# fitnessBuddy-TOP.net
KiCad netlist of a schematic drawn in EAGLE
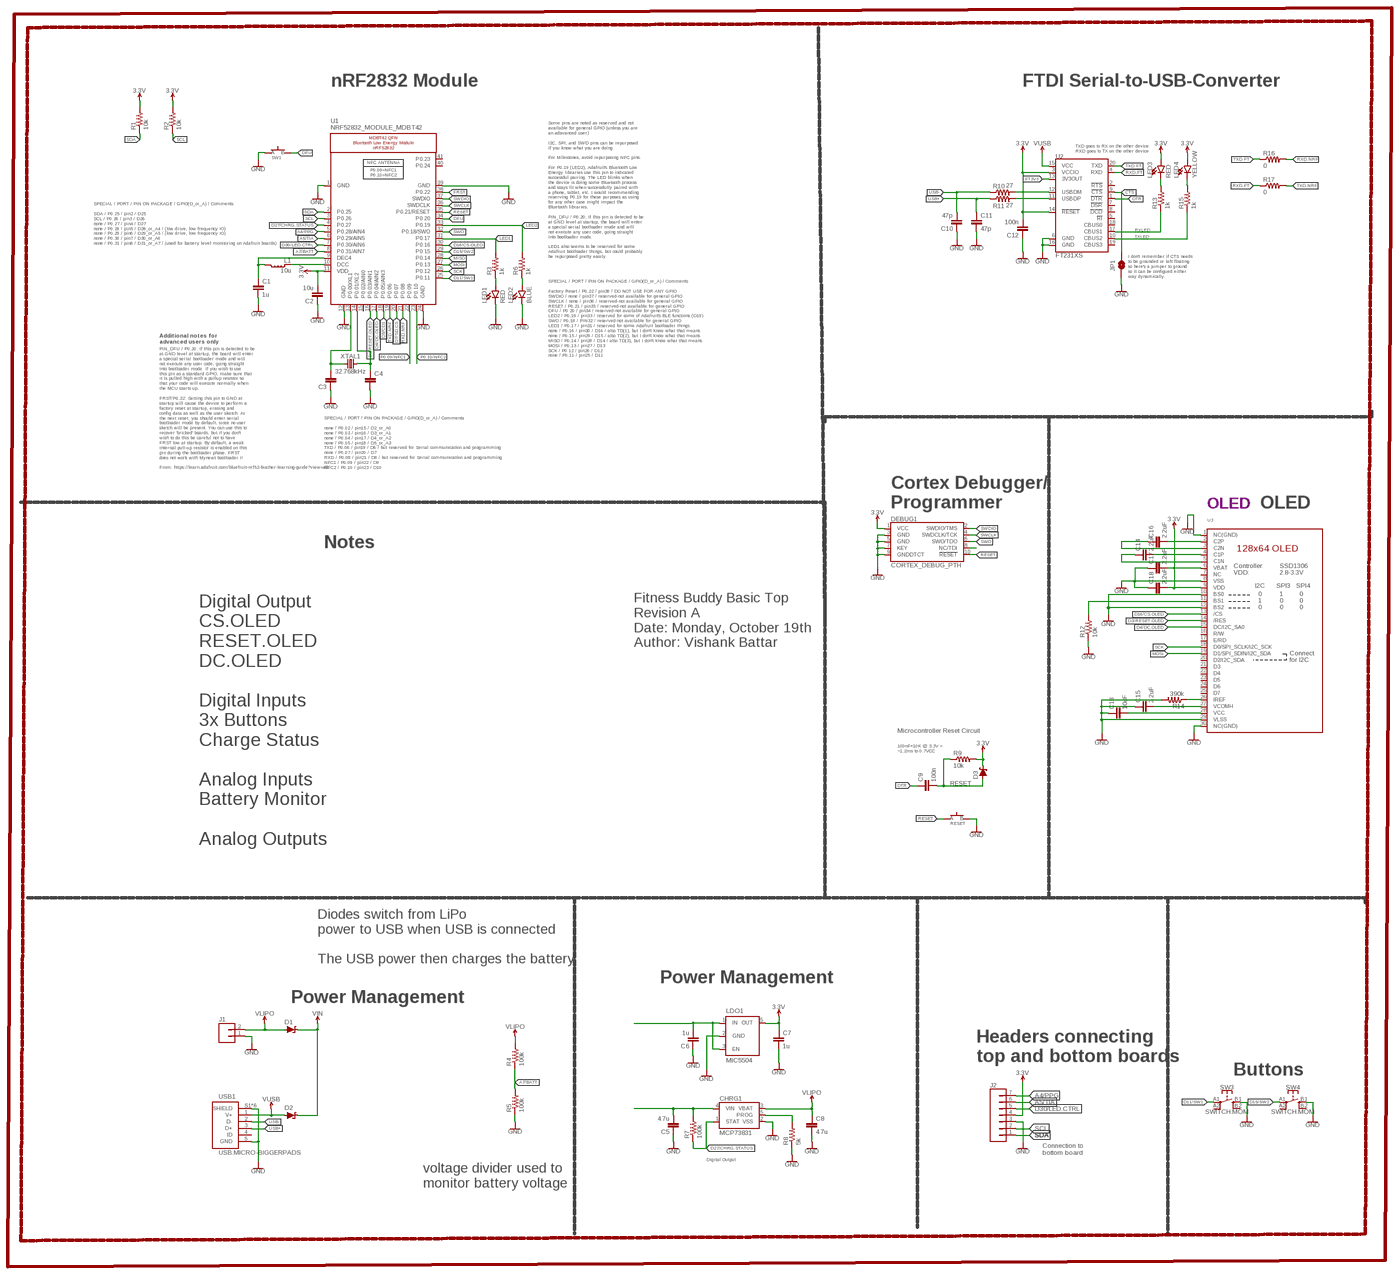
[diagram p0: schematic, sheet 1, overview]
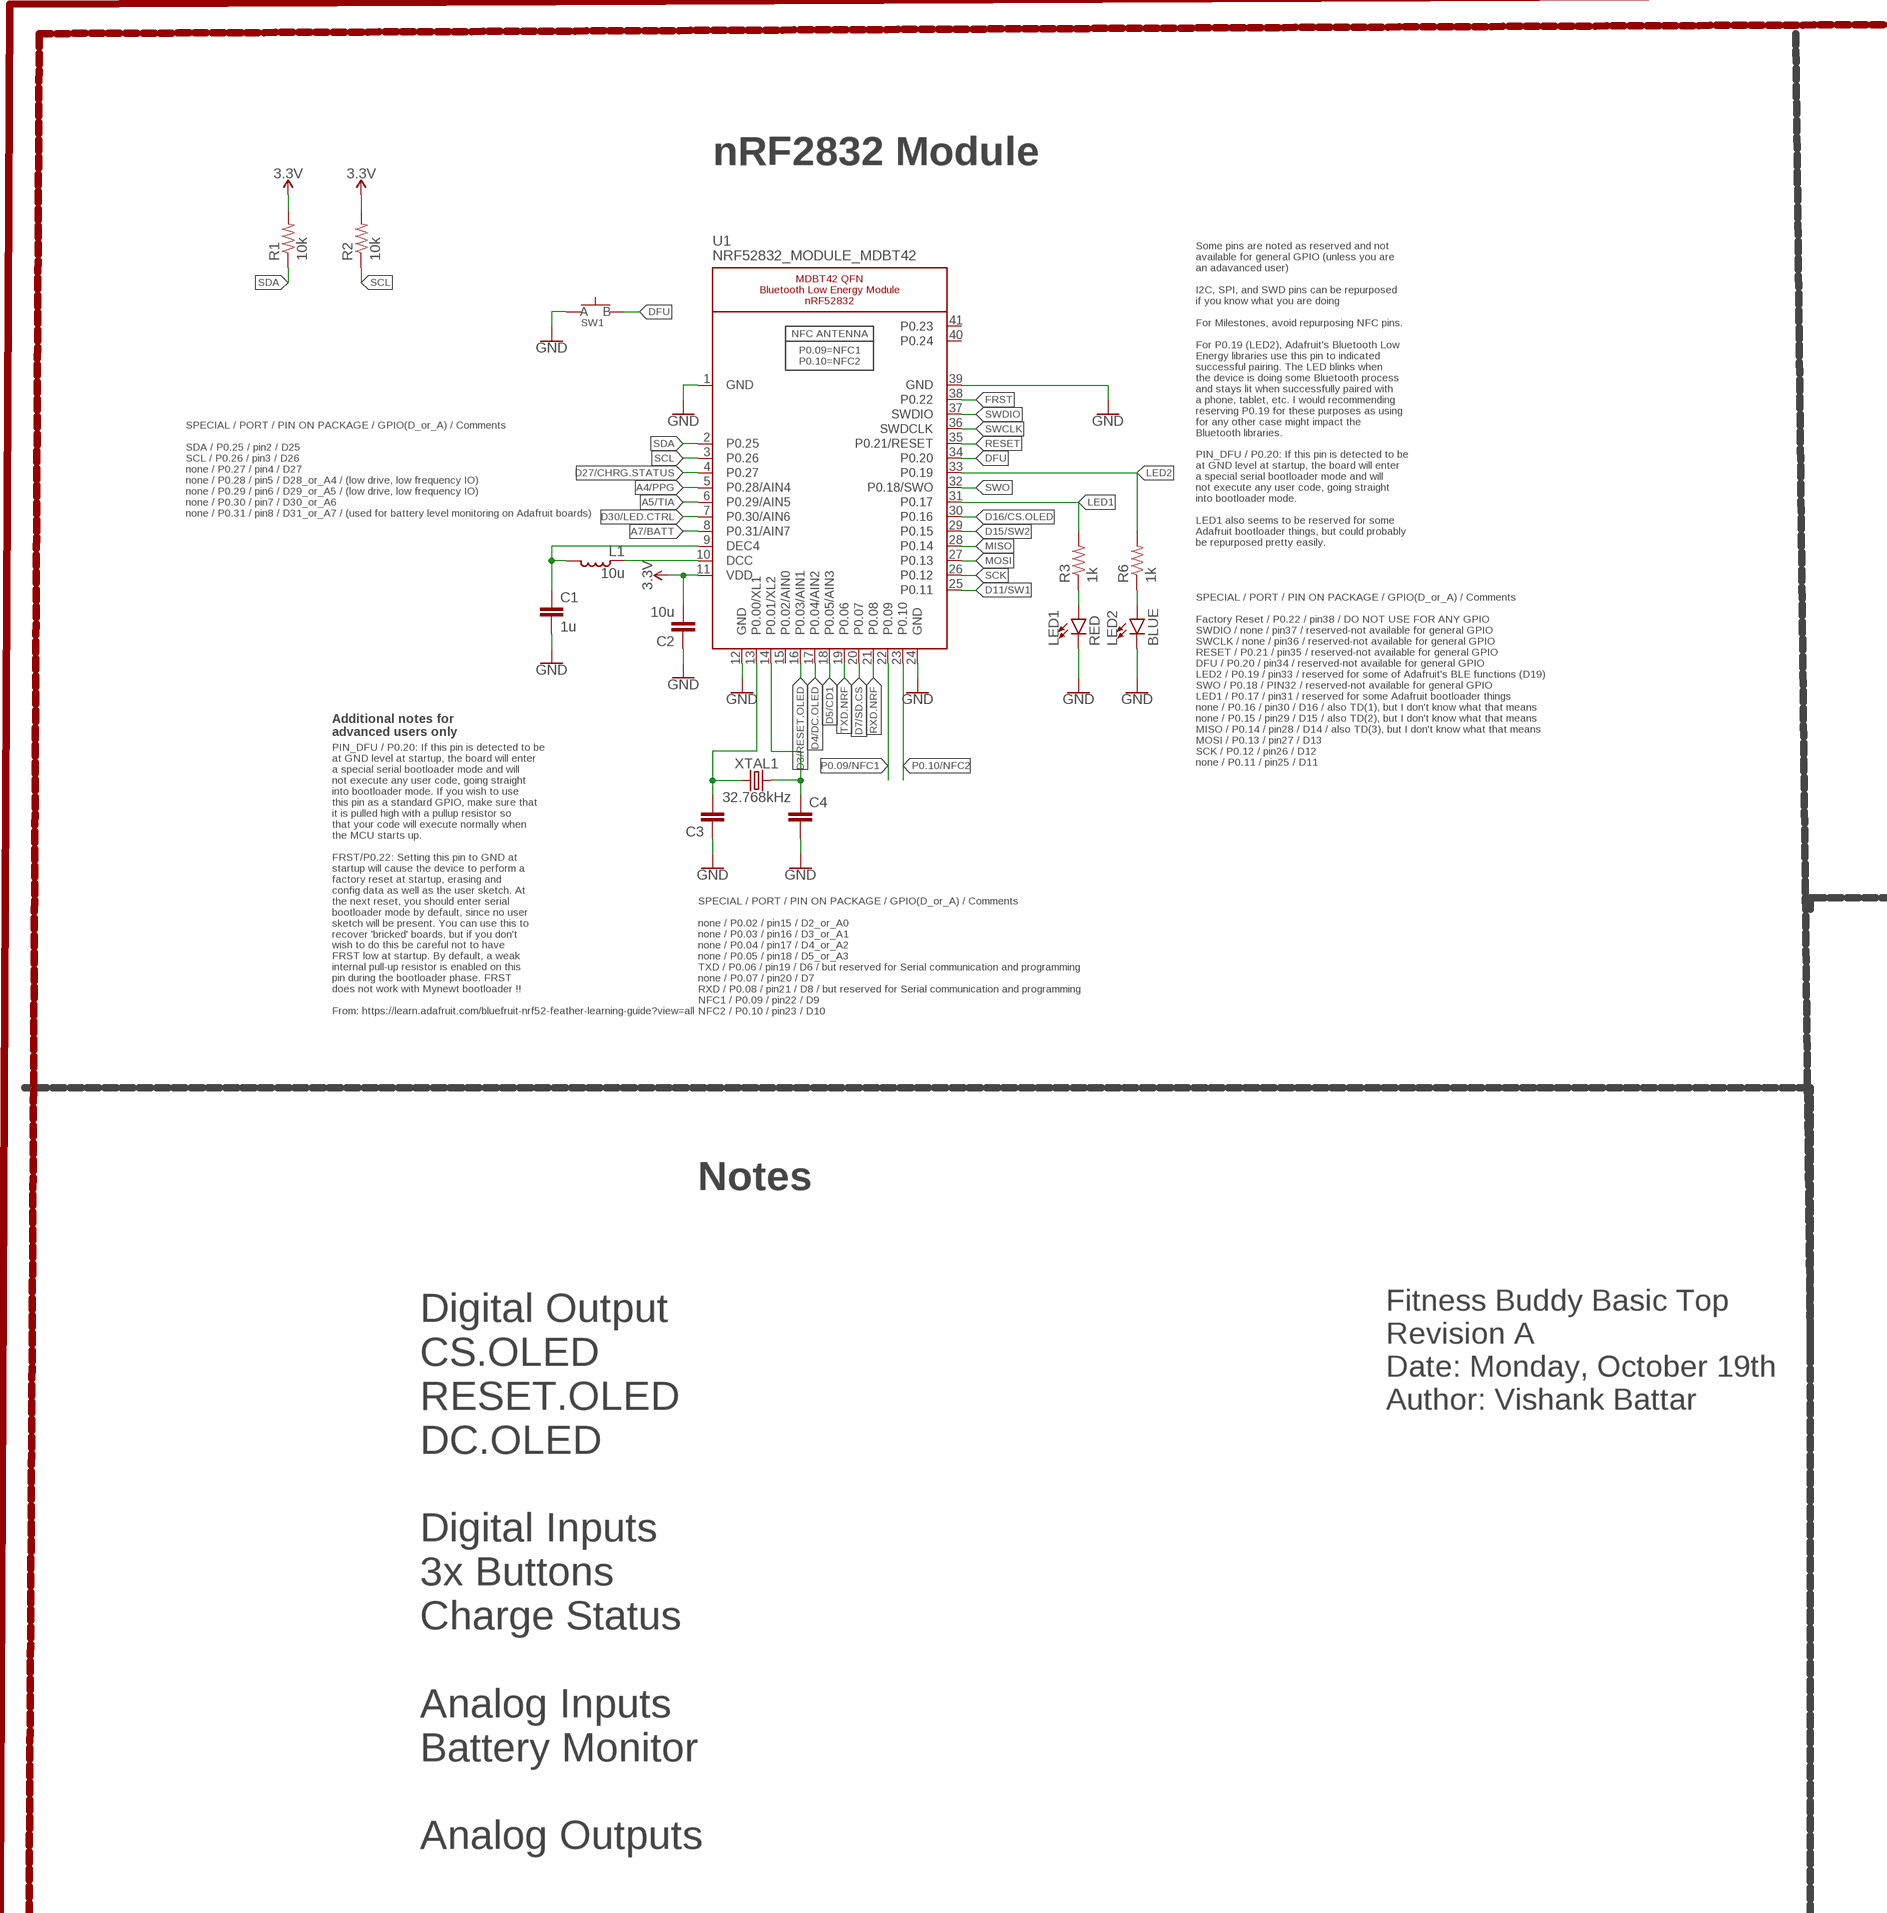
[diagram p1: schematic, sheet 1, part 1 of 4]
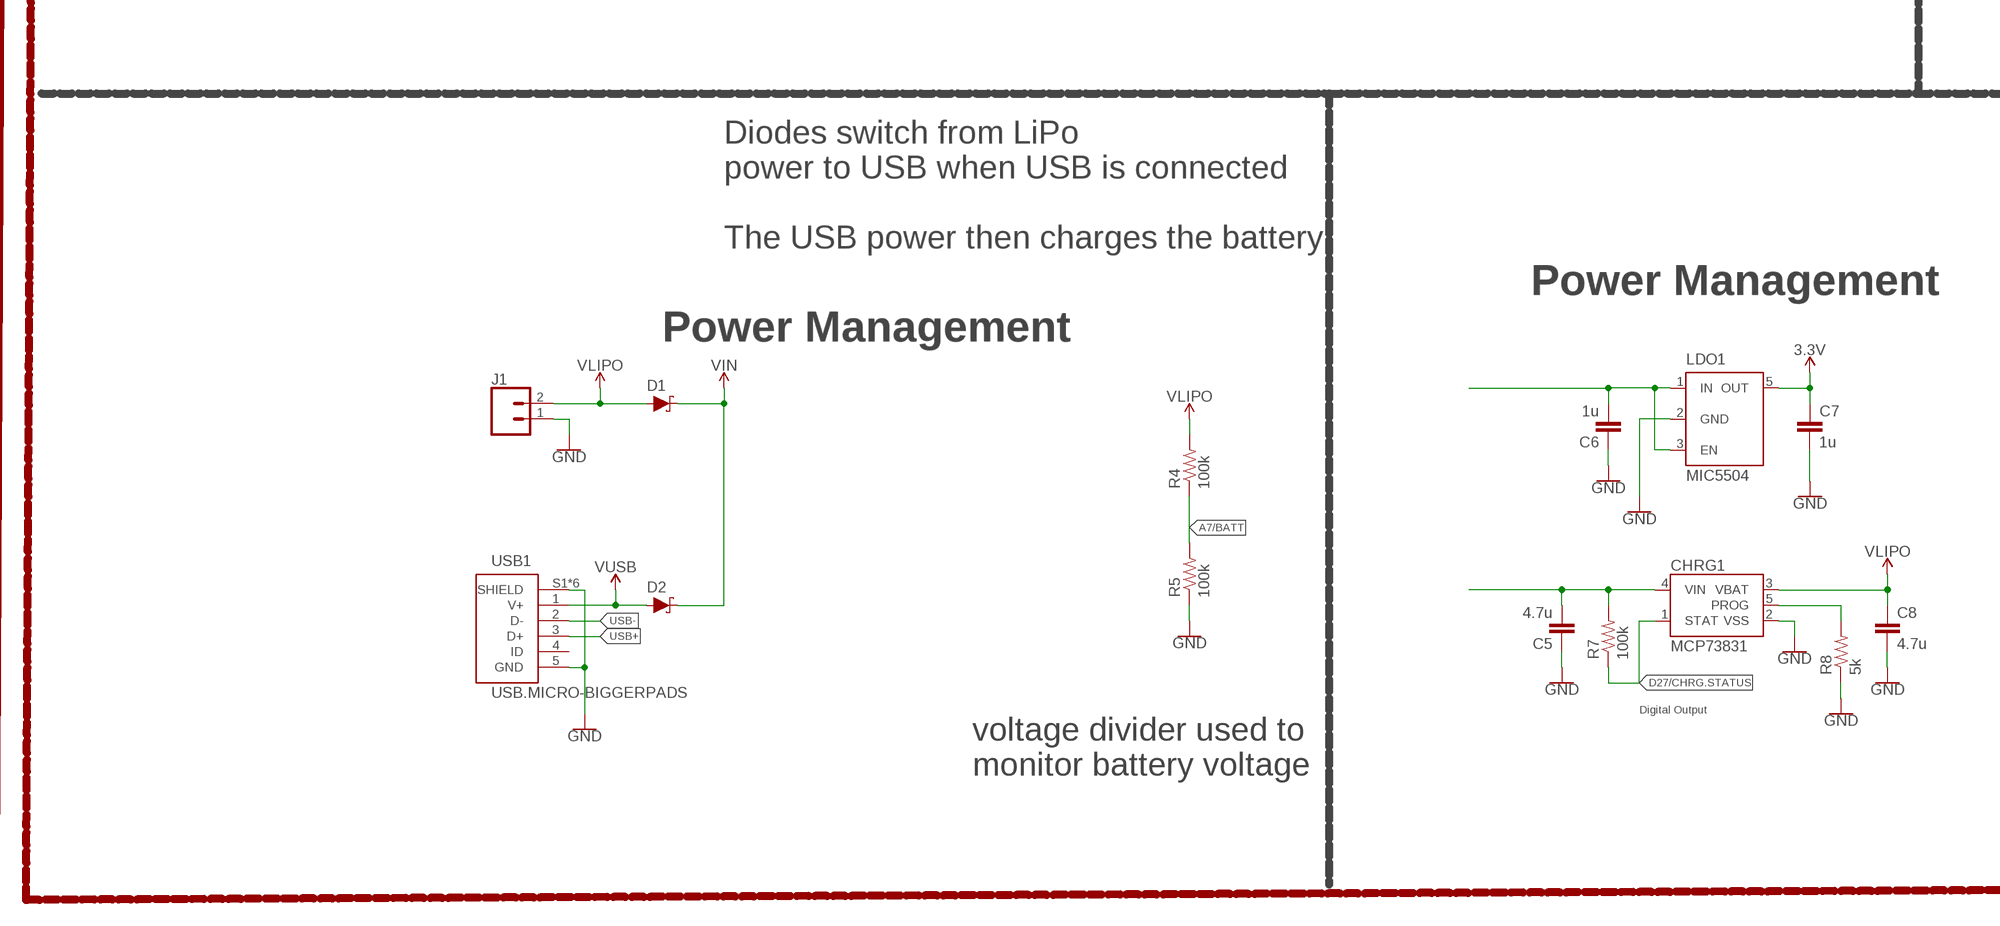
[diagram p2: schematic, sheet 1, part 2 of 4]
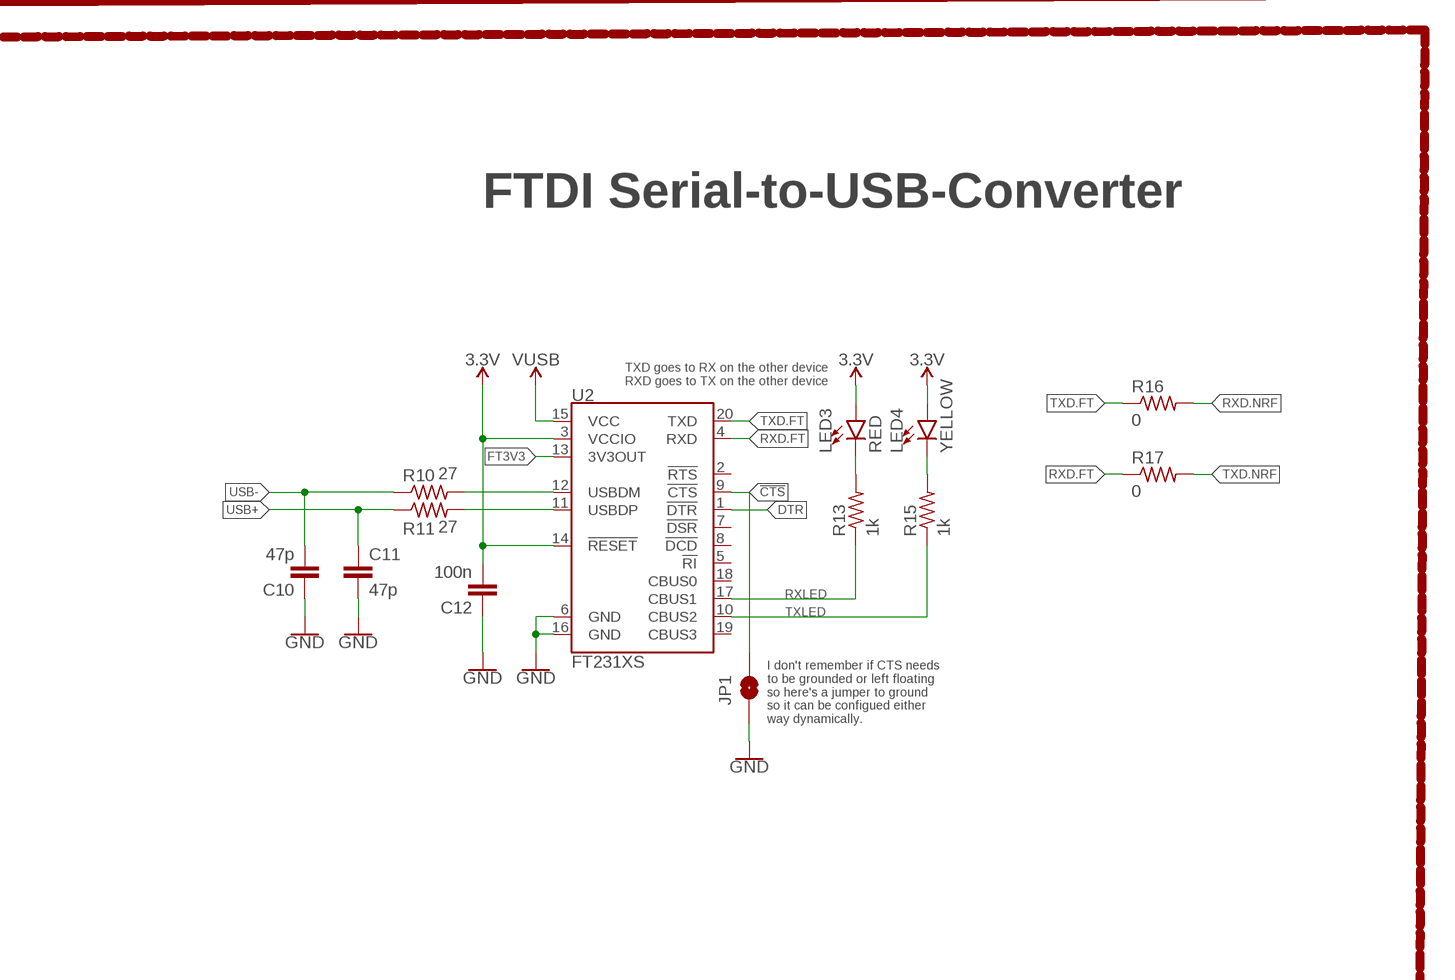
[diagram p3: schematic, sheet 1, part 3 of 4]
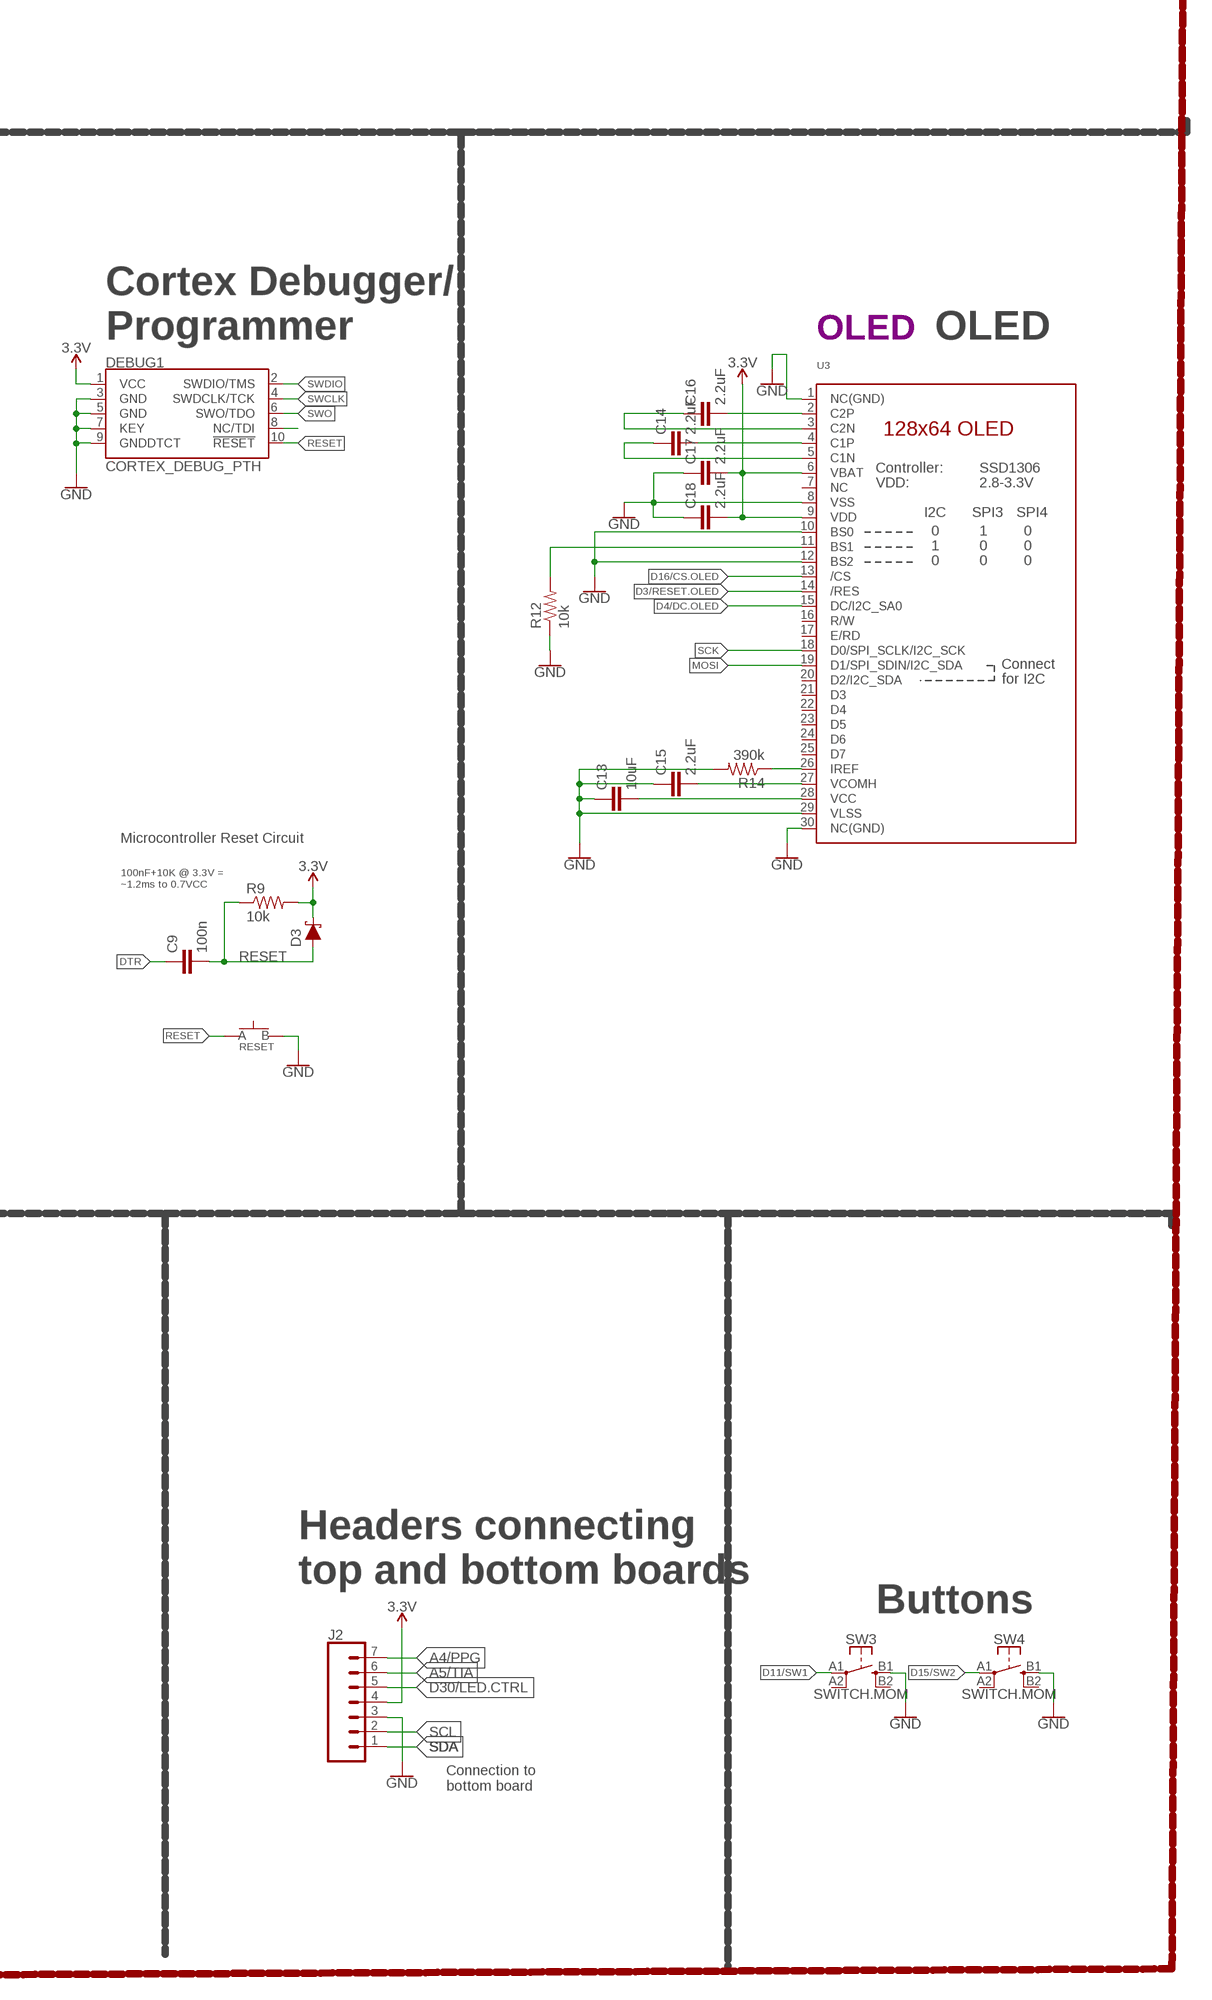
[diagram p4: schematic, sheet 1, part 4 of 4]

(export (version "E")
  (design (tool "Eeschema 10.0.6"))
  (components
    (comp (ref "C1")
      (value "1u")
      (footprint "eagle-import:C0603")
      (libsource (lib "eagle-import") (part "CAPACITOR0603"))
    )
    (comp (ref "C2")
      (value "10u")
      (footprint "eagle-import:C0805")
      (libsource (lib "eagle-import") (part "CAPACITOR0805"))
    )
    (comp (ref "C3")
      (value "CAPACITOR0603")
      (footprint "eagle-import:C0603")
      (libsource (lib "eagle-import") (part "CAPACITOR0603"))
    )
    (comp (ref "C4")
      (value "CAPACITOR0603")
      (footprint "eagle-import:C0603")
      (libsource (lib "eagle-import") (part "CAPACITOR0603"))
    )
    (comp (ref "C5")
      (value "4.7u")
      (footprint "eagle-import:C0603")
      (libsource (lib "eagle-import") (part "CAPACITOR0603"))
    )
    (comp (ref "C6")
      (value "1u")
      (footprint "eagle-import:C0603")
      (libsource (lib "eagle-import") (part "CAPACITOR0603"))
    )
    (comp (ref "C7")
      (value "1u")
      (footprint "eagle-import:C0603")
      (libsource (lib "eagle-import") (part "CAPACITOR0603"))
    )
    (comp (ref "C8")
      (value "4.7u")
      (footprint "eagle-import:C0603")
      (libsource (lib "eagle-import") (part "CAPACITOR0603"))
    )
    (comp (ref "C9")
      (value "100n")
      (footprint "eagle-import:C0603")
      (libsource (lib "eagle-import") (part "CAPACITOR0603"))
    )
    (comp (ref "C10")
      (value "47p")
      (footprint "eagle-import:C0603")
      (libsource (lib "eagle-import") (part "CAPACITOR0603"))
    )
    (comp (ref "C11")
      (value "47p")
      (footprint "eagle-import:C0603")
      (libsource (lib "eagle-import") (part "CAPACITOR0603"))
    )
    (comp (ref "C12")
      (value "100n")
      (footprint "eagle-import:C0603")
      (libsource (lib "eagle-import") (part "CAPACITOR0603"))
    )
    (comp (ref "C13")
      (value "10uF")
      (footprint "eagle-import:C0603")
      (libsource (lib "eagle-import") (part "CAPACITOR0603"))
    )
    (comp (ref "C14")
      (value "2.2uF")
      (footprint "eagle-import:C0402")
      (libsource (lib "eagle-import") (part "CAPACITOR0402"))
    )
    (comp (ref "C15")
      (value "2.2uF")
      (footprint "eagle-import:C0603")
      (libsource (lib "eagle-import") (part "CAPACITOR0603"))
    )
    (comp (ref "C16")
      (value "2.2uF")
      (footprint "eagle-import:C0402")
      (libsource (lib "eagle-import") (part "CAPACITOR0402"))
    )
    (comp (ref "C17")
      (value "2.2uF")
      (footprint "eagle-import:C0402")
      (libsource (lib "eagle-import") (part "CAPACITOR0402"))
    )
    (comp (ref "C18")
      (value "2.2uF")
      (footprint "eagle-import:C0402")
      (libsource (lib "eagle-import") (part "CAPACITOR0402"))
    )
    (comp (ref "CHRG1")
      (value "MCP73831")
      (footprint "eagle-import:SOT23-5")
      (libsource (lib "eagle-import") (part "MCP73831"))
    )
    (comp (ref "D1")
      (value "SCHOTTKY-USC")
      (footprint "eagle-import:USC")
      (libsource (lib "eagle-import") (part "SCHOTTKY-USC"))
    )
    (comp (ref "D2")
      (value "SCHOTTKY-USC")
      (footprint "eagle-import:USC")
      (libsource (lib "eagle-import") (part "SCHOTTKY-USC"))
    )
    (comp (ref "D3")
      (value "SCHOTTKY-USC")
      (footprint "eagle-import:USC")
      (libsource (lib "eagle-import") (part "SCHOTTKY-USC"))
    )
    (comp (ref "DEBUG1")
      (value "CORTEX_DEBUG_PTH")
      (footprint "eagle-import:2X5-PTH-1.27MM")
      (libsource (lib "eagle-import") (part "CORTEX_DEBUG_PTH"))
    )
    (comp (ref "J1")
      (value "CONN_02")
      (footprint "eagle-import:1X02")
      (libsource (lib "eagle-import") (part "CONN_02"))
    )
    (comp (ref "J2")
      (value "CONN_07-1.27MM")
      (footprint "eagle-import:1X07_1.27MM")
      (libsource (lib "eagle-import") (part "CONN_07-1.27MM"))
    )
    (comp (ref "JP1")
      (value "JUMPER-SMT_2_NO_SILK")
      (footprint "eagle-import:SMT-JUMPER_2_NO_SILK")
      (libsource (lib "eagle-import") (part "JUMPER-SMT_2_NO_SILK"))
    )
    (comp (ref "L1")
      (value "10u")
      (footprint "eagle-import:L0603")
      (libsource (lib "eagle-import") (part "INDUCTOR0603"))
    )
    (comp (ref "LDO1")
      (value "MIC5504")
      (footprint "eagle-import:SOT23-5")
      (libsource (lib "eagle-import") (part "MIC5504"))
    )
    (comp (ref "LED1")
      (value "RED")
      (footprint "eagle-import:LED-0603")
      (libsource (lib "eagle-import") (part "LED0603"))
    )
    (comp (ref "LED2")
      (value "BLUE")
      (footprint "eagle-import:LED-0603")
      (libsource (lib "eagle-import") (part "LED0603"))
    )
    (comp (ref "LED3")
      (value "RED")
      (footprint "eagle-import:LED-0603")
      (libsource (lib "eagle-import") (part "LED0603"))
    )
    (comp (ref "LED4")
      (value "YELLOW")
      (footprint "eagle-import:LED-0603")
      (libsource (lib "eagle-import") (part "LED0603"))
    )
    (comp (ref "R1")
      (value "10k")
      (footprint "eagle-import:R0603")
      (libsource (lib "eagle-import") (part "RESISTOR0603"))
    )
    (comp (ref "R2")
      (value "10k")
      (footprint "eagle-import:R0603")
      (libsource (lib "eagle-import") (part "RESISTOR0603"))
    )
    (comp (ref "R3")
      (value "1k")
      (footprint "eagle-import:R0603")
      (libsource (lib "eagle-import") (part "RESISTOR0603"))
    )
    (comp (ref "R4")
      (value "100k")
      (footprint "eagle-import:R0603")
      (libsource (lib "eagle-import") (part "RESISTOR0603"))
    )
    (comp (ref "R5")
      (value "100k")
      (footprint "eagle-import:R0603")
      (libsource (lib "eagle-import") (part "RESISTOR0603"))
    )
    (comp (ref "R6")
      (value "1k")
      (footprint "eagle-import:R0603")
      (libsource (lib "eagle-import") (part "RESISTOR0603"))
    )
    (comp (ref "R7")
      (value "100k")
      (footprint "eagle-import:R0603")
      (libsource (lib "eagle-import") (part "RESISTOR0603"))
    )
    (comp (ref "R8")
      (value "5k")
      (footprint "eagle-import:R0603")
      (libsource (lib "eagle-import") (part "RESISTOR0603"))
    )
    (comp (ref "R9")
      (value "10k")
      (footprint "eagle-import:R0603")
      (libsource (lib "eagle-import") (part "RESISTOR0603"))
    )
    (comp (ref "R10")
      (value "27")
      (footprint "eagle-import:R0603")
      (libsource (lib "eagle-import") (part "RESISTOR0603"))
    )
    (comp (ref "R11")
      (value "27")
      (footprint "eagle-import:R0603")
      (libsource (lib "eagle-import") (part "RESISTOR0603"))
    )
    (comp (ref "R12")
      (value "10k")
      (footprint "eagle-import:R0603")
      (libsource (lib "eagle-import") (part "RESISTOR0603"))
    )
    (comp (ref "R13")
      (value "1k")
      (footprint "eagle-import:R0603")
      (libsource (lib "eagle-import") (part "RESISTOR0603"))
    )
    (comp (ref "R14")
      (value "390k")
      (footprint "eagle-import:R0603")
      (libsource (lib "eagle-import") (part "RESISTOR0603"))
    )
    (comp (ref "R15")
      (value "1k")
      (footprint "eagle-import:R0603")
      (libsource (lib "eagle-import") (part "RESISTOR0603"))
    )
    (comp (ref "R16")
      (value "0")
      (footprint "eagle-import:R0603")
      (libsource (lib "eagle-import") (part "RESISTOR0603"))
    )
    (comp (ref "R17")
      (value "0")
      (footprint "eagle-import:R0603")
      (libsource (lib "eagle-import") (part "RESISTOR0603"))
    )
    (comp (ref "RESET")
      (value "SPST-PTS830GG140-COPY.1-3")
      (footprint "eagle-import:BUTTON-GULLWING")
      (libsource (lib "eagle-import") (part "SPST-PTS830GG140-COPY.1-3"))
    )
    (comp (ref "SW1")
      (value "SPST-PTS830GG140-COPY.1-3")
      (footprint "eagle-import:BUTTON-GULLWING")
      (libsource (lib "eagle-import") (part "SPST-PTS830GG140-COPY.1-3"))
    )
    (comp (ref "SW3")
      (value "SWITCH.MOM")
      (footprint "eagle-import:TACTILE_SWITCH_SMD_6.2MM_TALL")
      (libsource (lib "eagle-import") (part "SWITCH.MOM"))
    )
    (comp (ref "SW4")
      (value "SWITCH.MOM")
      (footprint "eagle-import:TACTILE_SWITCH_SMD_6.2MM_TALL")
      (libsource (lib "eagle-import") (part "SWITCH.MOM"))
    )
    (comp (ref "U1")
      (value "NRF52832_MODULE_MDBT42")
      (footprint "eagle-import:BLE_MODULE_RAYTAC_MDBT42")
      (libsource (lib "eagle-import") (part "NRF52832_MODULE_MDBT42"))
    )
    (comp (ref "U2")
      (value "FT231XS")
      (footprint "eagle-import:SSOP20_L")
      (libsource (lib "eagle-import") (part "FT231XS"))
    )
    (comp (ref "U3")
      (value "DISP_OLED_UG-2864HSWEG01-NO-WRAPAROUND")
      (footprint "eagle-import:UG-2864HSWEG01_0.96IN_NO-WRAPAROUND")
      (libsource (lib "eagle-import") (part "DISP_OLED_UG-2864HSWEG01-NO-WRAPAROUND"))
    )
    (comp (ref "USB1")
      (value "USB.MICRO-BIGGERPADS")
      (footprint "eagle-import:USB-MICRO-01.BIGGERPADS")
      (libsource (lib "eagle-import") (part "USB.MICRO-BIGGERPADS"))
    )
    (comp (ref "XTAL1")
      (value "32.768kHz")
      (footprint "eagle-import:2-SMD.NOLEAD.2.0MMTO1.2MM")
      (libsource (lib "eagle-import") (part "CRYSTALECS-.327-12.5-12-C-TR"))
    )
  )
  (nets
    (net (code "1") (name "/RXLED") (class "Default")
      (node (ref "R13") (pin "1") (pinfunction "1_1") (pintype "passive"))
      (node (ref "U2") (pin "17") (pinfunction "CBUS1_17") (pintype "bidirectional"))
    )
    (net (code "2") (name "/TXLED") (class "Default")
      (node (ref "R15") (pin "1") (pinfunction "1_1") (pintype "passive"))
      (node (ref "U2") (pin "10") (pinfunction "CBUS2_10") (pintype "bidirectional"))
    )
    (net (code "3") (name "/~{CTS}") (class "Default")
      (node (ref "JP1") (pin "2") (pinfunction "2_2") (pintype "passive"))
      (node (ref "U2") (pin "9") (pinfunction "~{CTS}_9") (pintype "bidirectional"))
    )
    (net (code "4") (name "3.3V") (class "Default")
      (node (ref "C12") (pin "2") (pinfunction "2_2") (pintype "passive"))
      (node (ref "C17") (pin "2") (pinfunction "2_2") (pintype "passive"))
      (node (ref "C18") (pin "2") (pinfunction "2_2") (pintype "passive"))
      (node (ref "C2") (pin "2") (pinfunction "2_2") (pintype "passive"))
      (node (ref "C7") (pin "1") (pinfunction "1_1") (pintype "passive"))
      (node (ref "D3") (pin "-") (pinfunction "C_-") (pintype "passive"))
      (node (ref "DEBUG1") (pin "1") (pinfunction "VCC_1") (pintype "bidirectional"))
      (node (ref "J2") (pin "4") (pinfunction "4_4") (pintype "passive"))
      (node (ref "LDO1") (pin "5") (pinfunction "OUT_5") (pintype "bidirectional"))
      (node (ref "LED3") (pin "A") (pinfunction "A_A") (pintype "passive"))
      (node (ref "LED4") (pin "A") (pinfunction "A_A") (pintype "passive"))
      (node (ref "R1") (pin "2") (pinfunction "2_2") (pintype "passive"))
      (node (ref "R2") (pin "2") (pinfunction "2_2") (pintype "passive"))
      (node (ref "R9") (pin "2") (pinfunction "2_2") (pintype "passive"))
      (node (ref "U1") (pin "11") (pinfunction "VDD_11") (pintype "bidirectional"))
      (node (ref "U2") (pin "14") (pinfunction "~{RESET}_14") (pintype "bidirectional"))
      (node (ref "U2") (pin "3") (pinfunction "VCCIO_3") (pintype "bidirectional"))
      (node (ref "U3") (pin "6") (pinfunction "VBAT_6") (pintype "input"))
      (node (ref "U3") (pin "9") (pinfunction "VDD_9") (pintype "power_in"))
    )
    (net (code "5") (name "A4{slash}PPG") (class "Default")
      (node (ref "J2") (pin "7") (pinfunction "7_7") (pintype "passive"))
      (node (ref "U1") (pin "5") (pinfunction "P0.28/AIN4_5") (pintype "bidirectional"))
    )
    (net (code "6") (name "A5{slash}TIA") (class "Default")
      (node (ref "J2") (pin "6") (pinfunction "6_6") (pintype "passive"))
      (node (ref "U1") (pin "6") (pinfunction "P0.29/AIN5_6") (pintype "bidirectional"))
    )
    (net (code "7") (name "A7{slash}BATT") (class "Default")
      (node (ref "R4") (pin "1") (pinfunction "1_1") (pintype "passive"))
      (node (ref "R5") (pin "2") (pinfunction "2_2") (pintype "passive"))
      (node (ref "U1") (pin "8") (pinfunction "P0.31/AIN7_8") (pintype "bidirectional"))
    )
    (net (code "8") (name "D3{slash}RESET.OLED") (class "Default")
      (node (ref "U1") (pin "16") (pinfunction "P0.03/AIN1_16") (pintype "bidirectional"))
      (node (ref "U3") (pin "14") (pinfunction "/RES_14") (pintype "input"))
    )
    (net (code "9") (name "D4{slash}DC.OLED") (class "Default")
      (node (ref "U1") (pin "17") (pinfunction "P0.04/AIN2_17") (pintype "bidirectional"))
      (node (ref "U3") (pin "15") (pinfunction "DC/I2C_SA0_15") (pintype "input"))
    )
    (net (code "10") (name "D5{slash}CD1") (class "Default")
      (node (ref "U1") (pin "18") (pinfunction "P0.05/AIN3_18") (pintype "bidirectional"))
    )
    (net (code "11") (name "D7{slash}SD.CS") (class "Default")
      (node (ref "U1") (pin "20") (pinfunction "P0.07_20") (pintype "bidirectional"))
    )
    (net (code "12") (name "D11{slash}SW1") (class "Default")
      (node (ref "SW3") (pin "A1") (pinfunction "1_A1") (pintype "passive"))
      (node (ref "U1") (pin "25") (pinfunction "P0.11_25") (pintype "bidirectional"))
    )
    (net (code "13") (name "D15{slash}SW2") (class "Default")
      (node (ref "SW4") (pin "A1") (pinfunction "1_A1") (pintype "passive"))
      (node (ref "U1") (pin "29") (pinfunction "P0.15_29") (pintype "bidirectional"))
    )
    (net (code "14") (name "D16{slash}CS.OLED") (class "Default")
      (node (ref "U1") (pin "30") (pinfunction "P0.16_30") (pintype "bidirectional"))
      (node (ref "U3") (pin "13") (pinfunction "/CS_13") (pintype "input"))
    )
    (net (code "15") (name "D27{slash}CHRG.STATUS") (class "Default")
      (node (ref "CHRG1") (pin "1") (pinfunction "STAT_1") (pintype "output"))
      (node (ref "R7") (pin "1") (pinfunction "1_1") (pintype "passive"))
      (node (ref "U1") (pin "4") (pinfunction "P0.27_4") (pintype "bidirectional"))
    )
    (net (code "16") (name "D30{slash}LED.CTRL") (class "Default")
      (node (ref "J2") (pin "5") (pinfunction "5_5") (pintype "passive"))
      (node (ref "U1") (pin "7") (pinfunction "P0.30/AIN6_7") (pintype "bidirectional"))
    )
    (net (code "17") (name "DFU") (class "Default")
      (node (ref "SW1") (pin "3") (pinfunction "B_3") (pintype "bidirectional"))
      (node (ref "U1") (pin "34") (pinfunction "P0.20_34") (pintype "bidirectional"))
    )
    (net (code "18") (name "DTR") (class "Default")
      (node (ref "C9") (pin "1") (pinfunction "1_1") (pintype "passive"))
      (node (ref "U2") (pin "1") (pinfunction "~{DTR}_1") (pintype "bidirectional"))
    )
    (net (code "19") (name "FRST") (class "Default")
      (node (ref "U1") (pin "38") (pinfunction "P0.22_38") (pintype "bidirectional"))
    )
    (net (code "20") (name "FT3V3") (class "Default")
      (node (ref "U2") (pin "13") (pinfunction "3V3OUT_13") (pintype "bidirectional"))
    )
    (net (code "21") (name "GND") (class "Default")
      (node (ref "C1") (pin "2") (pinfunction "2_2") (pintype "passive"))
      (node (ref "C10") (pin "1") (pinfunction "1_1") (pintype "passive"))
      (node (ref "C11") (pin "2") (pinfunction "2_2") (pintype "passive"))
      (node (ref "C12") (pin "1") (pinfunction "1_1") (pintype "passive"))
      (node (ref "C13") (pin "1") (pinfunction "1_1") (pintype "passive"))
      (node (ref "C15") (pin "1") (pinfunction "1_1") (pintype "passive"))
      (node (ref "C17") (pin "1") (pinfunction "1_1") (pintype "passive"))
      (node (ref "C18") (pin "1") (pinfunction "1_1") (pintype "passive"))
      (node (ref "C2") (pin "1") (pinfunction "1_1") (pintype "passive"))
      (node (ref "C3") (pin "1") (pinfunction "1_1") (pintype "passive"))
      (node (ref "C4") (pin "2") (pinfunction "2_2") (pintype "passive"))
      (node (ref "C5") (pin "1") (pinfunction "1_1") (pintype "passive"))
      (node (ref "C6") (pin "1") (pinfunction "1_1") (pintype "passive"))
      (node (ref "C7") (pin "2") (pinfunction "2_2") (pintype "passive"))
      (node (ref "C8") (pin "2") (pinfunction "2_2") (pintype "passive"))
      (node (ref "CHRG1") (pin "2") (pinfunction "VSS_2") (pintype "power_in"))
      (node (ref "DEBUG1") (pin "3") (pinfunction "GND_3") (pintype "bidirectional"))
      (node (ref "DEBUG1") (pin "5") (pinfunction "GND_5") (pintype "bidirectional"))
      (node (ref "DEBUG1") (pin "7") (pinfunction "KEY_7") (pintype "bidirectional"))
      (node (ref "DEBUG1") (pin "9") (pinfunction "GNDDTCT_9") (pintype "bidirectional"))
      (node (ref "J1") (pin "1") (pinfunction "1_1") (pintype "passive"))
      (node (ref "J2") (pin "3") (pinfunction "3_3") (pintype "passive"))
      (node (ref "JP1") (pin "1") (pinfunction "1_1") (pintype "passive"))
      (node (ref "LDO1") (pin "2") (pinfunction "GND_2") (pintype "bidirectional"))
      (node (ref "LED1") (pin "C") (pinfunction "C_C") (pintype "passive"))
      (node (ref "LED2") (pin "C") (pinfunction "C_C") (pintype "passive"))
      (node (ref "R12") (pin "1") (pinfunction "1_1") (pintype "passive"))
      (node (ref "R14") (pin "2") (pinfunction "2_2") (pintype "passive"))
      (node (ref "R5") (pin "1") (pinfunction "1_1") (pintype "passive"))
      (node (ref "R8") (pin "1") (pinfunction "1_1") (pintype "passive"))
      (node (ref "RESET") (pin "3") (pinfunction "B_3") (pintype "bidirectional"))
      (node (ref "SW1") (pin "1") (pinfunction "A_1") (pintype "bidirectional"))
      (node (ref "SW3") (pin "B1") (pinfunction "3_B1") (pintype "passive"))
      (node (ref "SW4") (pin "B1") (pinfunction "3_B1") (pintype "passive"))
      (node (ref "U1") (pin "1") (pinfunction "GND_1") (pintype "bidirectional"))
      (node (ref "U1") (pin "12") (pinfunction "GND_12") (pintype "bidirectional"))
      (node (ref "U1") (pin "24") (pinfunction "GND_24") (pintype "bidirectional"))
      (node (ref "U1") (pin "39") (pinfunction "GND_39") (pintype "bidirectional"))
      (node (ref "U2") (pin "16") (pinfunction "GND_16") (pintype "bidirectional"))
      (node (ref "U2") (pin "6") (pinfunction "GND_6") (pintype "bidirectional"))
      (node (ref "U3") (pin "1") (pinfunction "NC(GND)_1") (pintype "input"))
      (node (ref "U3") (pin "10") (pinfunction "BS0_10") (pintype "input"))
      (node (ref "U3") (pin "12") (pinfunction "BS2_12") (pintype "input"))
      (node (ref "U3") (pin "29") (pinfunction "VLSS_29") (pintype "power_in"))
      (node (ref "U3") (pin "30") (pinfunction "NC(GND)_30") (pintype "input"))
      (node (ref "U3") (pin "8") (pinfunction "VSS_8") (pintype "power_in"))
      (node (ref "USB1") (pin "5") (pinfunction "GND_5") (pintype "bidirectional"))
      (node (ref "USB1") (pin "S1") (pinfunction "SHIELD_S1") (pintype "bidirectional"))
      (node (ref "USB1") (pin "S2") (pinfunction "SHIELD_S2") (pintype "bidirectional"))
      (node (ref "USB1") (pin "S3") (pinfunction "SHIELD_S3") (pintype "bidirectional"))
      (node (ref "USB1") (pin "S4") (pinfunction "SHIELD_S4") (pintype "bidirectional"))
      (node (ref "USB1") (pin "S5") (pinfunction "SHIELD_S5") (pintype "bidirectional"))
      (node (ref "USB1") (pin "S6") (pinfunction "SHIELD_S6") (pintype "bidirectional"))
    )
    (net (code "22") (name "LED1") (class "Default")
      (node (ref "R3") (pin "2") (pinfunction "2_2") (pintype "passive"))
      (node (ref "U1") (pin "31") (pinfunction "P0.17_31") (pintype "bidirectional"))
    )
    (net (code "23") (name "LED2") (class "Default")
      (node (ref "R6") (pin "2") (pinfunction "2_2") (pintype "passive"))
      (node (ref "U1") (pin "33") (pinfunction "P0.19_33") (pintype "bidirectional"))
    )
    (net (code "24") (name "MISO") (class "Default")
      (node (ref "U1") (pin "28") (pinfunction "P0.14_28") (pintype "bidirectional"))
    )
    (net (code "25") (name "MOSI") (class "Default")
      (node (ref "U1") (pin "27") (pinfunction "P0.13_27") (pintype "bidirectional"))
      (node (ref "U3") (pin "19") (pinfunction "D1/SPI_SDIN/I2C_SDA_19") (pintype "bidirectional"))
    )
    (net (code "26") (name "Net-(CHRG1-PROG)") (class "Default")
      (node (ref "CHRG1") (pin "5") (pinfunction "PROG_5") (pintype "input"))
      (node (ref "R8") (pin "2") (pinfunction "2_2") (pintype "passive"))
    )
    (net (code "27") (name "Net-(CHRG1-VIN)") (class "Default")
      (node (ref "C5") (pin "2") (pinfunction "2_2") (pintype "passive"))
      (node (ref "CHRG1") (pin "4") (pinfunction "VIN_4") (pintype "power_in"))
      (node (ref "R7") (pin "2") (pinfunction "2_2") (pintype "passive"))
    )
    (net (code "28") (name "Net-(LED1-PadA)") (class "Default")
      (node (ref "LED1") (pin "A") (pinfunction "A_A") (pintype "passive"))
      (node (ref "R3") (pin "1") (pinfunction "1_1") (pintype "passive"))
    )
    (net (code "29") (name "Net-(LED2-PadA)") (class "Default")
      (node (ref "LED2") (pin "A") (pinfunction "A_A") (pintype "passive"))
      (node (ref "R6") (pin "1") (pinfunction "1_1") (pintype "passive"))
    )
    (net (code "30") (name "Net-(LED3-PadC)") (class "Default")
      (node (ref "LED3") (pin "C") (pinfunction "C_C") (pintype "passive"))
      (node (ref "R13") (pin "2") (pinfunction "2_2") (pintype "passive"))
    )
    (net (code "31") (name "Net-(LED4-PadC)") (class "Default")
      (node (ref "LED4") (pin "C") (pinfunction "C_C") (pintype "passive"))
      (node (ref "R15") (pin "2") (pinfunction "2_2") (pintype "passive"))
    )
    (net (code "32") (name "Net-(U1-DCC)") (class "Default")
      (node (ref "L1") (pin "1") (pinfunction "1_1") (pintype "passive"))
      (node (ref "U1") (pin "10") (pinfunction "DCC_10") (pintype "bidirectional"))
    )
    (net (code "33") (name "Net-(U1-DEC4)") (class "Default")
      (node (ref "C1") (pin "1") (pinfunction "1_1") (pintype "passive"))
      (node (ref "L1") (pin "2") (pinfunction "2_2") (pintype "passive"))
      (node (ref "U1") (pin "9") (pinfunction "DEC4_9") (pintype "bidirectional"))
    )
    (net (code "34") (name "Net-(U1-P0.00{slash}XL1)") (class "Default")
      (node (ref "C3") (pin "2") (pinfunction "2_2") (pintype "passive"))
      (node (ref "U1") (pin "13") (pinfunction "P0.00/XL1_13") (pintype "bidirectional"))
      (node (ref "XTAL1") (pin "P$1") (pinfunction "1_P$1") (pintype "passive"))
    )
    (net (code "35") (name "Net-(U1-P0.01{slash}XL2)") (class "Default")
      (node (ref "C4") (pin "1") (pinfunction "1_1") (pintype "passive"))
      (node (ref "U1") (pin "14") (pinfunction "P0.01/XL2_14") (pintype "bidirectional"))
      (node (ref "XTAL1") (pin "P$2") (pinfunction "2_P$2") (pintype "passive"))
    )
    (net (code "36") (name "Net-(U2-USBDM)") (class "Default")
      (node (ref "R10") (pin "2") (pinfunction "2_2") (pintype "passive"))
      (node (ref "U2") (pin "12") (pinfunction "USBDM_12") (pintype "bidirectional"))
    )
    (net (code "37") (name "Net-(U2-USBDP)") (class "Default")
      (node (ref "R11") (pin "2") (pinfunction "2_2") (pintype "passive"))
      (node (ref "U2") (pin "11") (pinfunction "USBDP_11") (pintype "bidirectional"))
    )
    (net (code "38") (name "Net-(U3-BS1)") (class "Default")
      (node (ref "R12") (pin "2") (pinfunction "2_2") (pintype "passive"))
      (node (ref "U3") (pin "11") (pinfunction "BS1_11") (pintype "input"))
    )
    (net (code "39") (name "Net-(U3-C1N)") (class "Default")
      (node (ref "C14") (pin "1") (pinfunction "1_1") (pintype "passive"))
      (node (ref "U3") (pin "5") (pinfunction "C1N_5") (pintype "input"))
    )
    (net (code "40") (name "Net-(U3-C1P)") (class "Default")
      (node (ref "C14") (pin "2") (pinfunction "2_2") (pintype "passive"))
      (node (ref "U3") (pin "4") (pinfunction "C1P_4") (pintype "input"))
    )
    (net (code "41") (name "Net-(U3-C2N)") (class "Default")
      (node (ref "C16") (pin "1") (pinfunction "1_1") (pintype "passive"))
      (node (ref "U3") (pin "3") (pinfunction "C2N_3") (pintype "input"))
    )
    (net (code "42") (name "Net-(U3-C2P)") (class "Default")
      (node (ref "C16") (pin "2") (pinfunction "2_2") (pintype "passive"))
      (node (ref "U3") (pin "2") (pinfunction "C2P_2") (pintype "input"))
    )
    (net (code "43") (name "Net-(U3-IREF)") (class "Default")
      (node (ref "R14") (pin "1") (pinfunction "1_1") (pintype "passive"))
      (node (ref "U3") (pin "26") (pinfunction "IREF_26") (pintype "input"))
    )
    (net (code "44") (name "Net-(U3-VCC)") (class "Default")
      (node (ref "C13") (pin "2") (pinfunction "2_2") (pintype "passive"))
      (node (ref "U3") (pin "28") (pinfunction "VCC_28") (pintype "power_in"))
    )
    (net (code "45") (name "Net-(U3-VCOMH)") (class "Default")
      (node (ref "C15") (pin "2") (pinfunction "2_2") (pintype "passive"))
      (node (ref "U3") (pin "27") (pinfunction "VCOMH_27") (pintype "output"))
    )
    (net (code "46") (name "P0.09{slash}NFC1") (class "Default")
      (node (ref "U1") (pin "22") (pinfunction "P0.09_22") (pintype "bidirectional"))
    )
    (net (code "47") (name "P0.10{slash}NFC2") (class "Default")
      (node (ref "U1") (pin "23") (pinfunction "P0.10_23") (pintype "bidirectional"))
    )
    (net (code "48") (name "RESET") (class "Default")
      (node (ref "C9") (pin "2") (pinfunction "2_2") (pintype "passive"))
      (node (ref "D3") (pin "+") (pinfunction "A_+") (pintype "passive"))
      (node (ref "DEBUG1") (pin "10") (pinfunction "~{RESET}_10") (pintype "bidirectional"))
      (node (ref "R9") (pin "1") (pinfunction "1_1") (pintype "passive"))
      (node (ref "RESET") (pin "1") (pinfunction "A_1") (pintype "bidirectional"))
      (node (ref "U1") (pin "35") (pinfunction "P0.21/RESET_35") (pintype "bidirectional"))
    )
    (net (code "49") (name "RXD.FT") (class "Default")
      (node (ref "R17") (pin "1") (pinfunction "1_1") (pintype "passive"))
      (node (ref "U2") (pin "4") (pinfunction "RXD_4") (pintype "bidirectional"))
    )
    (net (code "50") (name "RXD.NRF") (class "Default")
      (node (ref "R16") (pin "2") (pinfunction "2_2") (pintype "passive"))
      (node (ref "U1") (pin "21") (pinfunction "P0.08_21") (pintype "bidirectional"))
    )
    (net (code "51") (name "SCK") (class "Default")
      (node (ref "U1") (pin "26") (pinfunction "P0.12_26") (pintype "bidirectional"))
      (node (ref "U3") (pin "18") (pinfunction "D0/SPI_SCLK/I2C_SCK_18") (pintype "bidirectional"))
    )
    (net (code "52") (name "SCL") (class "Default")
      (node (ref "J2") (pin "2") (pinfunction "2_2") (pintype "passive"))
      (node (ref "R2") (pin "1") (pinfunction "1_1") (pintype "passive"))
      (node (ref "U1") (pin "3") (pinfunction "P0.26_3") (pintype "bidirectional"))
    )
    (net (code "53") (name "SDA") (class "Default")
      (node (ref "J2") (pin "1") (pinfunction "1_1") (pintype "passive"))
      (node (ref "R1") (pin "1") (pinfunction "1_1") (pintype "passive"))
      (node (ref "U1") (pin "2") (pinfunction "P0.25_2") (pintype "bidirectional"))
    )
    (net (code "54") (name "SWCLK") (class "Default")
      (node (ref "DEBUG1") (pin "4") (pinfunction "SWDCLK/TCK_4") (pintype "bidirectional"))
      (node (ref "U1") (pin "36") (pinfunction "SWDCLK_36") (pintype "bidirectional"))
    )
    (net (code "55") (name "SWDIO") (class "Default")
      (node (ref "DEBUG1") (pin "2") (pinfunction "SWDIO/TMS_2") (pintype "bidirectional"))
      (node (ref "U1") (pin "37") (pinfunction "SWDIO_37") (pintype "bidirectional"))
    )
    (net (code "56") (name "SWO") (class "Default")
      (node (ref "DEBUG1") (pin "6") (pinfunction "SWO/TDO_6") (pintype "bidirectional"))
      (node (ref "U1") (pin "32") (pinfunction "P0.18/SWO_32") (pintype "bidirectional"))
    )
    (net (code "57") (name "TXD.FT") (class "Default")
      (node (ref "R16") (pin "1") (pinfunction "1_1") (pintype "passive"))
      (node (ref "U2") (pin "20") (pinfunction "TXD_20") (pintype "bidirectional"))
    )
    (net (code "58") (name "TXD.NRF") (class "Default")
      (node (ref "R17") (pin "2") (pinfunction "2_2") (pintype "passive"))
      (node (ref "U1") (pin "19") (pinfunction "P0.06_19") (pintype "bidirectional"))
    )
    (net (code "59") (name "USB+") (class "Default")
      (node (ref "C11") (pin "1") (pinfunction "1_1") (pintype "passive"))
      (node (ref "R11") (pin "1") (pinfunction "1_1") (pintype "passive"))
      (node (ref "USB1") (pin "3") (pinfunction "D+_3") (pintype "bidirectional"))
    )
    (net (code "60") (name "USB-") (class "Default")
      (node (ref "C10") (pin "2") (pinfunction "2_2") (pintype "passive"))
      (node (ref "R10") (pin "1") (pinfunction "1_1") (pintype "passive"))
      (node (ref "USB1") (pin "2") (pinfunction "D-_2") (pintype "bidirectional"))
    )
    (net (code "61") (name "VIN") (class "Default")
      (node (ref "C6") (pin "2") (pinfunction "2_2") (pintype "passive"))
      (node (ref "D1") (pin "-") (pinfunction "C_-") (pintype "passive"))
      (node (ref "D2") (pin "-") (pinfunction "C_-") (pintype "passive"))
      (node (ref "LDO1") (pin "1") (pinfunction "IN_1") (pintype "bidirectional"))
      (node (ref "LDO1") (pin "3") (pinfunction "EN_3") (pintype "bidirectional"))
    )
    (net (code "62") (name "VLIPO") (class "Default")
      (node (ref "C8") (pin "1") (pinfunction "1_1") (pintype "passive"))
      (node (ref "CHRG1") (pin "3") (pinfunction "VBAT_3") (pintype "power_in"))
      (node (ref "D1") (pin "+") (pinfunction "A_+") (pintype "passive"))
      (node (ref "J1") (pin "2") (pinfunction "2_2") (pintype "passive"))
      (node (ref "R4") (pin "2") (pinfunction "2_2") (pintype "passive"))
    )
    (net (code "63") (name "VUSB") (class "Default")
      (node (ref "D2") (pin "+") (pinfunction "A_+") (pintype "passive"))
      (node (ref "U2") (pin "15") (pinfunction "VCC_15") (pintype "bidirectional"))
      (node (ref "USB1") (pin "1") (pinfunction "V+_1") (pintype "bidirectional"))
    )
    (net (code "64") (name "unconnected-(DEBUG1-NC{slash}TDI-Pad8)") (class "Default")
      (node (ref "DEBUG1") (pin "8") (pinfunction "NC/TDI_8") (pintype "bidirectional"))
    )
    (net (code "65") (name "unconnected-(SW3-2-PadA2)") (class "Default")
      (node (ref "SW3") (pin "A2") (pinfunction "2_A2") (pintype "passive"))
    )
    (net (code "66") (name "unconnected-(SW3-4-PadB2)") (class "Default")
      (node (ref "SW3") (pin "B2") (pinfunction "4_B2") (pintype "passive"))
    )
    (net (code "67") (name "unconnected-(SW4-2-PadA2)") (class "Default")
      (node (ref "SW4") (pin "A2") (pinfunction "2_A2") (pintype "passive"))
    )
    (net (code "68") (name "unconnected-(SW4-4-PadB2)") (class "Default")
      (node (ref "SW4") (pin "B2") (pinfunction "4_B2") (pintype "passive"))
    )
    (net (code "69") (name "unconnected-(U1-P0.02{slash}AIN0-Pad15)") (class "Default")
      (node (ref "U1") (pin "15") (pinfunction "P0.02/AIN0_15") (pintype "bidirectional"))
    )
    (net (code "70") (name "unconnected-(U1-P0.23-Pad41)") (class "Default")
      (node (ref "U1") (pin "41") (pinfunction "P0.23_41") (pintype "bidirectional"))
    )
    (net (code "71") (name "unconnected-(U1-P0.24-Pad40)") (class "Default")
      (node (ref "U1") (pin "40") (pinfunction "P0.24_40") (pintype "bidirectional"))
    )
    (net (code "72") (name "unconnected-(U2-CBUS0-Pad18)") (class "Default")
      (node (ref "U2") (pin "18") (pinfunction "CBUS0_18") (pintype "bidirectional"))
    )
    (net (code "73") (name "unconnected-(U2-CBUS3-Pad19)") (class "Default")
      (node (ref "U2") (pin "19") (pinfunction "CBUS3_19") (pintype "bidirectional"))
    )
    (net (code "74") (name "unconnected-(U2-~{DCD}-Pad8)") (class "Default")
      (node (ref "U2") (pin "8") (pinfunction "~{DCD}_8") (pintype "bidirectional"))
    )
    (net (code "75") (name "unconnected-(U2-~{DSR}-Pad7)") (class "Default")
      (node (ref "U2") (pin "7") (pinfunction "~{DSR}_7") (pintype "bidirectional"))
    )
    (net (code "76") (name "unconnected-(U2-~{RI}-Pad5)") (class "Default")
      (node (ref "U2") (pin "5") (pinfunction "~{RI}_5") (pintype "bidirectional"))
    )
    (net (code "77") (name "unconnected-(U2-~{RTS}-Pad2)") (class "Default")
      (node (ref "U2") (pin "2") (pinfunction "~{RTS}_2") (pintype "bidirectional"))
    )
    (net (code "78") (name "unconnected-(U3-D2{slash}I2C_SDA-Pad20)") (class "Default")
      (node (ref "U3") (pin "20") (pinfunction "D2/I2C_SDA_20") (pintype "bidirectional"))
    )
    (net (code "79") (name "unconnected-(U3-D3-Pad21)") (class "Default")
      (node (ref "U3") (pin "21") (pinfunction "D3_21") (pintype "bidirectional"))
    )
    (net (code "80") (name "unconnected-(U3-D4-Pad22)") (class "Default")
      (node (ref "U3") (pin "22") (pinfunction "D4_22") (pintype "bidirectional"))
    )
    (net (code "81") (name "unconnected-(U3-D5-Pad23)") (class "Default")
      (node (ref "U3") (pin "23") (pinfunction "D5_23") (pintype "bidirectional"))
    )
    (net (code "82") (name "unconnected-(U3-D6-Pad24)") (class "Default")
      (node (ref "U3") (pin "24") (pinfunction "D6_24") (pintype "bidirectional"))
    )
    (net (code "83") (name "unconnected-(U3-D7-Pad25)") (class "Default")
      (node (ref "U3") (pin "25") (pinfunction "D7_25") (pintype "bidirectional"))
    )
    (net (code "84") (name "unconnected-(U3-E{slash}RD-Pad17)") (class "Default")
      (node (ref "U3") (pin "17") (pinfunction "E/RD_17") (pintype "input"))
    )
    (net (code "85") (name "unconnected-(U3-NC-Pad7)") (class "Default")
      (node (ref "U3") (pin "7") (pinfunction "NC_7") (pintype "no_connect"))
    )
    (net (code "86") (name "unconnected-(U3-R{slash}W-Pad16)") (class "Default")
      (node (ref "U3") (pin "16") (pinfunction "R/W_16") (pintype "input"))
    )
    (net (code "87") (name "unconnected-(USB1-ID-Pad4)") (class "Default")
      (node (ref "USB1") (pin "4") (pinfunction "ID_4") (pintype "bidirectional"))
    )
  )
)
